# FLC-148_side_connector_panel.net
KiCad netlist of a schematic drawn in EAGLE
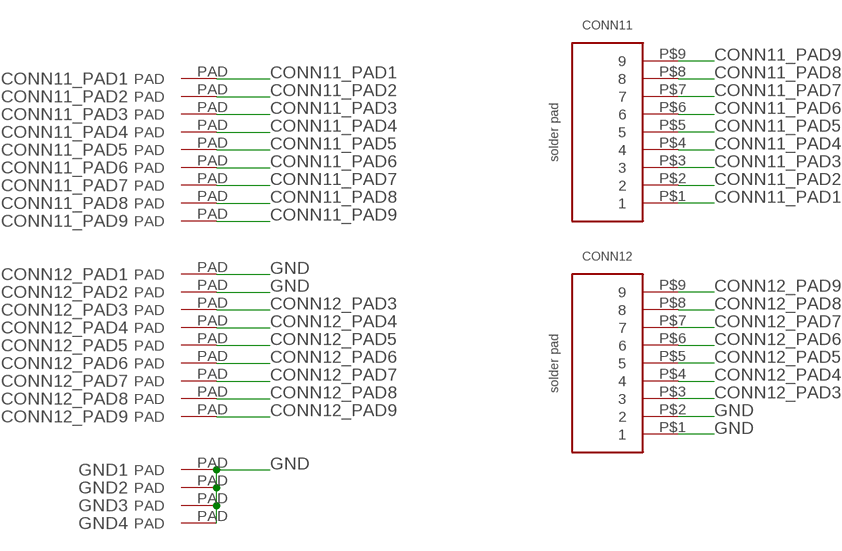
[diagram p0: schematic, sheet 1]

(export (version "E")
  (design (tool "Eeschema 10.0.6"))
  (components
    (comp (ref "CONN11")
      (value "solder pad")
      (footprint "eagle-import:FFC_1MM_9P")
      (libsource (lib "eagle-import") (part "FFC_1MM_9P"))
    )
    (comp (ref "CONN11_PAD1")
      (value "PAD")
      (footprint "eagle-import:PAD")
      (libsource (lib "eagle-import") (part "PAD"))
    )
    (comp (ref "CONN11_PAD2")
      (value "PAD")
      (footprint "eagle-import:PAD")
      (libsource (lib "eagle-import") (part "PAD"))
    )
    (comp (ref "CONN11_PAD3")
      (value "PAD")
      (footprint "eagle-import:PAD")
      (libsource (lib "eagle-import") (part "PAD"))
    )
    (comp (ref "CONN11_PAD4")
      (value "PAD")
      (footprint "eagle-import:PAD")
      (libsource (lib "eagle-import") (part "PAD"))
    )
    (comp (ref "CONN11_PAD5")
      (value "PAD")
      (footprint "eagle-import:PAD")
      (libsource (lib "eagle-import") (part "PAD"))
    )
    (comp (ref "CONN11_PAD6")
      (value "PAD")
      (footprint "eagle-import:PAD")
      (libsource (lib "eagle-import") (part "PAD"))
    )
    (comp (ref "CONN11_PAD7")
      (value "PAD")
      (footprint "eagle-import:PAD")
      (libsource (lib "eagle-import") (part "PAD"))
    )
    (comp (ref "CONN11_PAD8")
      (value "PAD")
      (footprint "eagle-import:PAD")
      (libsource (lib "eagle-import") (part "PAD"))
    )
    (comp (ref "CONN11_PAD9")
      (value "PAD")
      (footprint "eagle-import:PAD")
      (libsource (lib "eagle-import") (part "PAD"))
    )
    (comp (ref "CONN12")
      (value "solder pad")
      (footprint "eagle-import:FFC_1MM_9P")
      (libsource (lib "eagle-import") (part "FFC_1MM_9P"))
    )
    (comp (ref "CONN12_PAD1")
      (value "PAD")
      (footprint "eagle-import:PAD")
      (libsource (lib "eagle-import") (part "PAD"))
    )
    (comp (ref "CONN12_PAD2")
      (value "PAD")
      (footprint "eagle-import:PAD")
      (libsource (lib "eagle-import") (part "PAD"))
    )
    (comp (ref "CONN12_PAD3")
      (value "PAD")
      (footprint "eagle-import:PAD")
      (libsource (lib "eagle-import") (part "PAD"))
    )
    (comp (ref "CONN12_PAD4")
      (value "PAD")
      (footprint "eagle-import:PAD")
      (libsource (lib "eagle-import") (part "PAD"))
    )
    (comp (ref "CONN12_PAD5")
      (value "PAD")
      (footprint "eagle-import:PAD")
      (libsource (lib "eagle-import") (part "PAD"))
    )
    (comp (ref "CONN12_PAD6")
      (value "PAD")
      (footprint "eagle-import:PAD")
      (libsource (lib "eagle-import") (part "PAD"))
    )
    (comp (ref "CONN12_PAD7")
      (value "PAD")
      (footprint "eagle-import:PAD")
      (libsource (lib "eagle-import") (part "PAD"))
    )
    (comp (ref "CONN12_PAD8")
      (value "PAD")
      (footprint "eagle-import:PAD")
      (libsource (lib "eagle-import") (part "PAD"))
    )
    (comp (ref "CONN12_PAD9")
      (value "PAD")
      (footprint "eagle-import:PAD")
      (libsource (lib "eagle-import") (part "PAD"))
    )
    (comp (ref "GND1")
      (value "PAD")
      (footprint "eagle-import:PAD")
      (libsource (lib "eagle-import") (part "PAD"))
    )
    (comp (ref "GND2")
      (value "PAD")
      (footprint "eagle-import:PAD")
      (libsource (lib "eagle-import") (part "PAD"))
    )
    (comp (ref "GND3")
      (value "PAD")
      (footprint "eagle-import:PAD")
      (libsource (lib "eagle-import") (part "PAD"))
    )
    (comp (ref "GND4")
      (value "PAD")
      (footprint "eagle-import:PAD")
      (libsource (lib "eagle-import") (part "PAD"))
    )
  )
  (nets
    (net (code "1") (name "/CONN11_PAD1") (class "Default")
      (node (ref "CONN11") (pin "P$1") (pinfunction "1_P$1") (pintype "bidirectional"))
      (node (ref "CONN11_PAD1") (pin "PAD") (pinfunction "PAD_PAD") (pintype "bidirectional"))
    )
    (net (code "2") (name "/CONN11_PAD2") (class "Default")
      (node (ref "CONN11") (pin "P$2") (pinfunction "2_P$2") (pintype "bidirectional"))
      (node (ref "CONN11_PAD2") (pin "PAD") (pinfunction "PAD_PAD") (pintype "bidirectional"))
    )
    (net (code "3") (name "/CONN11_PAD3") (class "Default")
      (node (ref "CONN11") (pin "P$3") (pinfunction "3_P$3") (pintype "bidirectional"))
      (node (ref "CONN11_PAD3") (pin "PAD") (pinfunction "PAD_PAD") (pintype "bidirectional"))
    )
    (net (code "4") (name "/CONN11_PAD4") (class "Default")
      (node (ref "CONN11") (pin "P$4") (pinfunction "4_P$4") (pintype "bidirectional"))
      (node (ref "CONN11_PAD4") (pin "PAD") (pinfunction "PAD_PAD") (pintype "bidirectional"))
    )
    (net (code "5") (name "/CONN11_PAD5") (class "Default")
      (node (ref "CONN11") (pin "P$5") (pinfunction "5_P$5") (pintype "bidirectional"))
      (node (ref "CONN11_PAD5") (pin "PAD") (pinfunction "PAD_PAD") (pintype "bidirectional"))
    )
    (net (code "6") (name "/CONN11_PAD6") (class "Default")
      (node (ref "CONN11") (pin "P$6") (pinfunction "6_P$6") (pintype "bidirectional"))
      (node (ref "CONN11_PAD6") (pin "PAD") (pinfunction "PAD_PAD") (pintype "bidirectional"))
    )
    (net (code "7") (name "/CONN11_PAD7") (class "Default")
      (node (ref "CONN11") (pin "P$7") (pinfunction "7_P$7") (pintype "bidirectional"))
      (node (ref "CONN11_PAD7") (pin "PAD") (pinfunction "PAD_PAD") (pintype "bidirectional"))
    )
    (net (code "8") (name "/CONN11_PAD8") (class "Default")
      (node (ref "CONN11") (pin "P$8") (pinfunction "8_P$8") (pintype "bidirectional"))
      (node (ref "CONN11_PAD8") (pin "PAD") (pinfunction "PAD_PAD") (pintype "bidirectional"))
    )
    (net (code "9") (name "/CONN11_PAD9") (class "Default")
      (node (ref "CONN11") (pin "P$9") (pinfunction "9_P$9") (pintype "bidirectional"))
      (node (ref "CONN11_PAD9") (pin "PAD") (pinfunction "PAD_PAD") (pintype "bidirectional"))
    )
    (net (code "10") (name "/CONN12_PAD3") (class "Default")
      (node (ref "CONN12") (pin "P$3") (pinfunction "3_P$3") (pintype "bidirectional"))
      (node (ref "CONN12_PAD3") (pin "PAD") (pinfunction "PAD_PAD") (pintype "bidirectional"))
    )
    (net (code "11") (name "/CONN12_PAD4") (class "Default")
      (node (ref "CONN12") (pin "P$4") (pinfunction "4_P$4") (pintype "bidirectional"))
      (node (ref "CONN12_PAD4") (pin "PAD") (pinfunction "PAD_PAD") (pintype "bidirectional"))
    )
    (net (code "12") (name "/CONN12_PAD5") (class "Default")
      (node (ref "CONN12") (pin "P$5") (pinfunction "5_P$5") (pintype "bidirectional"))
      (node (ref "CONN12_PAD5") (pin "PAD") (pinfunction "PAD_PAD") (pintype "bidirectional"))
    )
    (net (code "13") (name "/CONN12_PAD6") (class "Default")
      (node (ref "CONN12") (pin "P$6") (pinfunction "6_P$6") (pintype "bidirectional"))
      (node (ref "CONN12_PAD6") (pin "PAD") (pinfunction "PAD_PAD") (pintype "bidirectional"))
    )
    (net (code "14") (name "/CONN12_PAD7") (class "Default")
      (node (ref "CONN12") (pin "P$7") (pinfunction "7_P$7") (pintype "bidirectional"))
      (node (ref "CONN12_PAD7") (pin "PAD") (pinfunction "PAD_PAD") (pintype "bidirectional"))
    )
    (net (code "15") (name "/CONN12_PAD8") (class "Default")
      (node (ref "CONN12") (pin "P$8") (pinfunction "8_P$8") (pintype "bidirectional"))
      (node (ref "CONN12_PAD8") (pin "PAD") (pinfunction "PAD_PAD") (pintype "bidirectional"))
    )
    (net (code "16") (name "/CONN12_PAD9") (class "Default")
      (node (ref "CONN12") (pin "P$9") (pinfunction "9_P$9") (pintype "bidirectional"))
      (node (ref "CONN12_PAD9") (pin "PAD") (pinfunction "PAD_PAD") (pintype "bidirectional"))
    )
    (net (code "17") (name "/GND") (class "Default")
      (node (ref "CONN12") (pin "P$1") (pinfunction "1_P$1") (pintype "bidirectional"))
      (node (ref "CONN12") (pin "P$2") (pinfunction "2_P$2") (pintype "bidirectional"))
      (node (ref "CONN12_PAD1") (pin "PAD") (pinfunction "PAD_PAD") (pintype "bidirectional"))
      (node (ref "CONN12_PAD2") (pin "PAD") (pinfunction "PAD_PAD") (pintype "bidirectional"))
      (node (ref "GND1") (pin "PAD") (pinfunction "PAD_PAD") (pintype "bidirectional"))
      (node (ref "GND2") (pin "PAD") (pinfunction "PAD_PAD") (pintype "bidirectional"))
      (node (ref "GND3") (pin "PAD") (pinfunction "PAD_PAD") (pintype "bidirectional"))
      (node (ref "GND4") (pin "PAD") (pinfunction "PAD_PAD") (pintype "bidirectional"))
    )
  )
)
